# OSO-SAFE-B1-03.net
KiCad netlist of a schematic drawn in EAGLE
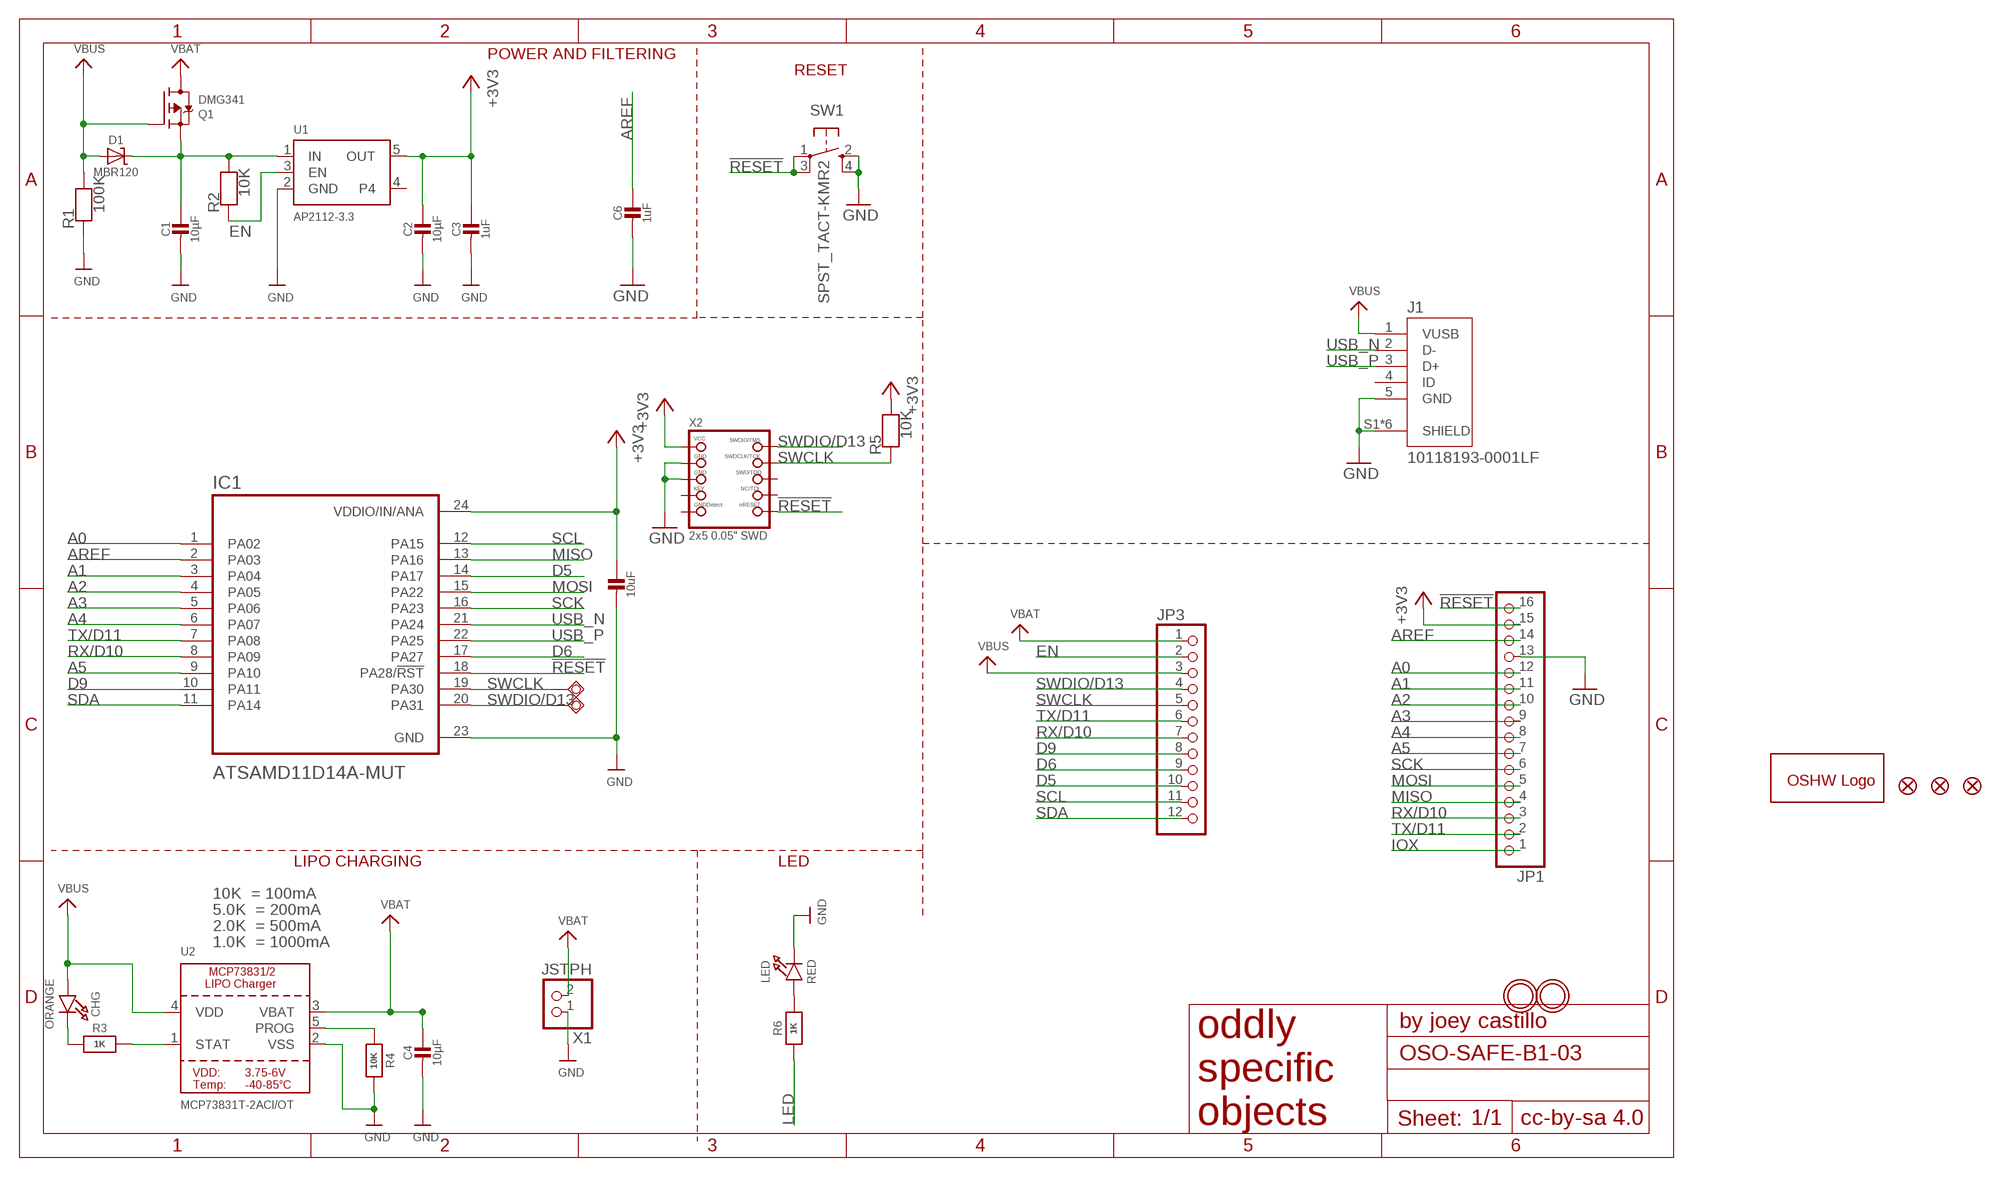
[diagram p0: schematic, sheet 1]

(export (version "E")
  (design (tool "Eeschema 10.0.6"))
  (components
    (comp (ref "C1")
      (value "10µF")
      (footprint "eagle-import:0805-NO")
      (libsource (lib "eagle-import") (part "CAP_CERAMIC0805-NOOUTLINE"))
    )
    (comp (ref "C2")
      (value "10µF")
      (footprint "eagle-import:0805-NO")
      (libsource (lib "eagle-import") (part "CAP_CERAMIC0805-NOOUTLINE"))
    )
    (comp (ref "C3")
      (value "1uF")
      (footprint "eagle-import:0805-NO")
      (libsource (lib "eagle-import") (part "CAP_CERAMIC0805-NOOUTLINE"))
    )
    (comp (ref "C4")
      (value "10µF")
      (footprint "eagle-import:0805-NO")
      (libsource (lib "eagle-import") (part "CAP_CERAMIC0805-NOOUTLINE"))
    )
    (comp (ref "C5")
      (value "10uF")
      (footprint "eagle-import:0805-NO")
      (libsource (lib "eagle-import") (part "CAP_CERAMIC0805-NOOUTLINE"))
    )
    (comp (ref "C6")
      (value "1uF")
      (footprint "eagle-import:0805-NO")
      (libsource (lib "eagle-import") (part "CAP_CERAMIC0805-NOOUTLINE"))
    )
    (comp (ref "CHG")
      (value "ORANGE")
      (footprint "eagle-import:CHIPLED_0805_NOOUTLINE")
      (libsource (lib "eagle-import") (part "LED0805_NOOUTLINE"))
    )
    (comp (ref "D1")
      (value "MBR120")
      (footprint "eagle-import:SOD-123")
      (libsource (lib "eagle-import") (part "DIODE-SCHOTTKYSOD-123"))
    )
    (comp (ref "FID1")
      (value "FIDUCIAL_1MM")
      (footprint "eagle-import:FIDUCIAL_1MM")
      (libsource (lib "eagle-import") (part "FIDUCIAL_1MM"))
    )
    (comp (ref "FID3")
      (value "FIDUCIAL_1MM")
      (footprint "eagle-import:FIDUCIAL_1MM")
      (libsource (lib "eagle-import") (part "FIDUCIAL_1MM"))
    )
    (comp (ref "FID4")
      (value "FIDUCIAL_1MM")
      (footprint "eagle-import:FIDUCIAL_1MM")
      (libsource (lib "eagle-import") (part "FIDUCIAL_1MM"))
    )
    (comp (ref "GOLD_ORB_SM1")
      (value "OSHWLOGOLOGO5MM")
      (footprint "eagle-import:OSHW_5MM")
      (libsource (lib "eagle-import") (part "OSHWLOGOLOGO5MM"))
    )
    (comp (ref "IC1")
      (value "ATSAMD11D14A-MUT")
      (footprint "eagle-import:QFN50P400X400X90-25N")
      (fields (field (name "MF") "Microchip"))
      (libsource (lib "eagle-import") (part "ATSAMD11D14A-MUT"))
    )
    (comp (ref "J1")
      (value "10118193-0001LF")
      (footprint "eagle-import:FCI_10118193-0001LF")
      (fields (field (name "DIGI-KEY_PART_NUMBER") "609-4616-1-ND") (field (name "MF") "Amphenol ICC"))
      (libsource (lib "eagle-import") (part "10118193-0001LF"))
    )
    (comp (ref "JP1")
      (value "HEADER-1X16_MIN")
      (footprint "eagle-import:1X16_ROUND_MIN")
      (libsource (lib "eagle-import") (part "HEADER-1X16_MIN"))
    )
    (comp (ref "JP3")
      (value "HEADER-1X12_MIN")
      (footprint "eagle-import:1X12_ROUND_MIN")
      (libsource (lib "eagle-import") (part "HEADER-1X12_MIN"))
    )
    (comp (ref "LED")
      (value "RED")
      (footprint "eagle-import:CHIPLED_0805_NOOUTLINE")
      (libsource (lib "eagle-import") (part "LED0805_NOOUTLINE"))
    )
    (comp (ref "Q1")
      (value "DMG341")
      (footprint "eagle-import:SOT23-R")
      (libsource (lib "eagle-import") (part "MOSFET-P"))
    )
    (comp (ref "R1")
      (value "100K")
      (footprint "eagle-import:0805-NO")
      (libsource (lib "eagle-import") (part "RESISTOR0805_NOOUTLINE"))
    )
    (comp (ref "R2")
      (value "10K")
      (footprint "eagle-import:0805-NO")
      (libsource (lib "eagle-import") (part "RESISTOR0805_NOOUTLINE"))
    )
    (comp (ref "R3")
      (value "1K")
      (footprint "eagle-import:0805-NO")
      (libsource (lib "eagle-import") (part "RESISTOR0805_NOOUTLINE"))
    )
    (comp (ref "R4")
      (value "10K")
      (footprint "eagle-import:0805-NO")
      (libsource (lib "eagle-import") (part "RESISTOR0805_NOOUTLINE"))
    )
    (comp (ref "R5")
      (value "10K")
      (footprint "eagle-import:0805-NO")
      (libsource (lib "eagle-import") (part "RESISTOR0805_NOOUTLINE"))
    )
    (comp (ref "R6")
      (value "1K")
      (footprint "eagle-import:0805-NO")
      (libsource (lib "eagle-import") (part "RESISTOR0805_NOOUTLINE"))
    )
    (comp (ref "SW1")
      (value "SPST_TACT-KMR2")
      (footprint "eagle-import:KMR2")
      (libsource (lib "eagle-import") (part "SPST_TACT-KMR2"))
    )
    (comp (ref "SWCLK")
      (value "TPSQTP20R")
      (footprint "eagle-import:TP20R")
      (libsource (lib "eagle-import") (part "TPSQTP20R"))
    )
    (comp (ref "SWDIO")
      (value "TPSQTP20R")
      (footprint "eagle-import:TP20R")
      (libsource (lib "eagle-import") (part "TPSQTP20R"))
    )
    (comp (ref "U$31")
      (value "MOUNTINGHOLE2.5")
      (footprint "eagle-import:MOUNTINGHOLE_2.5_PLATED")
      (libsource (lib "eagle-import") (part "MOUNTINGHOLE2.5"))
    )
    (comp (ref "U$32")
      (value "MOUNTINGHOLE2.5")
      (footprint "eagle-import:MOUNTINGHOLE_2.5_PLATED")
      (libsource (lib "eagle-import") (part "MOUNTINGHOLE2.5"))
    )
    (comp (ref "U1")
      (value "AP2112-3.3")
      (footprint "eagle-import:SOT23-5")
      (libsource (lib "eagle-import") (part "VREG_SOT23-5"))
    )
    (comp (ref "U2")
      (value "MCP73831T-2ACI/OT")
      (footprint "eagle-import:SOT23-5")
      (libsource (lib "eagle-import") (part "MCP73831/2"))
    )
    (comp (ref "X1")
      (value "JSTPH")
      (footprint "eagle-import:JSTPH2")
      (libsource (lib "eagle-import") (part "CON_JST_PH_2PIN"))
    )
    (comp (ref "X2")
      (value "2x5 0.05\" SWD")
      (footprint "eagle-import:2X05_1.27MM_BOX_POSTS")
      (libsource (lib "eagle-import") (part "JTAG-CORTEXBOXPOSTS"))
    )
  )
  (nets
    (net (code "1") (name "+3V3") (class "Default")
      (node (ref "C2") (pin "1") (pinfunction "1_1") (pintype "passive"))
      (node (ref "C3") (pin "1") (pinfunction "1_1") (pintype "passive"))
      (node (ref "C5") (pin "1") (pinfunction "1_1") (pintype "passive"))
      (node (ref "IC1") (pin "24") (pinfunction "VDDIO/IN/ANA_24") (pintype "power_in"))
      (node (ref "JP1") (pin "15") (pinfunction "15_15") (pintype "passive"))
      (node (ref "R5") (pin "2") (pinfunction "2_2") (pintype "passive"))
      (node (ref "U1") (pin "5") (pinfunction "OUT_5") (pintype "power_in"))
      (node (ref "X2") (pin "1") (pinfunction "VCC_1") (pintype "power_in"))
    )
    (net (code "2") (name "/A0") (class "Default")
      (node (ref "IC1") (pin "1") (pinfunction "PA02_1") (pintype "bidirectional"))
      (node (ref "JP1") (pin "12") (pinfunction "12_12") (pintype "passive"))
    )
    (net (code "3") (name "/A1") (class "Default")
      (node (ref "IC1") (pin "3") (pinfunction "PA04_3") (pintype "bidirectional"))
      (node (ref "JP1") (pin "11") (pinfunction "11_11") (pintype "passive"))
    )
    (net (code "4") (name "/A2") (class "Default")
      (node (ref "IC1") (pin "4") (pinfunction "PA05_4") (pintype "bidirectional"))
      (node (ref "JP1") (pin "10") (pinfunction "10_10") (pintype "passive"))
    )
    (net (code "5") (name "/A3") (class "Default")
      (node (ref "IC1") (pin "5") (pinfunction "PA06_5") (pintype "bidirectional"))
      (node (ref "JP1") (pin "9") (pinfunction "9_9") (pintype "passive"))
    )
    (net (code "6") (name "/A4") (class "Default")
      (node (ref "IC1") (pin "6") (pinfunction "PA07_6") (pintype "bidirectional"))
      (node (ref "JP1") (pin "8") (pinfunction "8_8") (pintype "passive"))
    )
    (net (code "7") (name "/A5") (class "Default")
      (node (ref "IC1") (pin "9") (pinfunction "PA10_9") (pintype "bidirectional"))
      (node (ref "JP1") (pin "7") (pinfunction "7_7") (pintype "passive"))
    )
    (net (code "8") (name "/AREF") (class "Default")
      (node (ref "C6") (pin "1") (pinfunction "1_1") (pintype "passive"))
      (node (ref "IC1") (pin "2") (pinfunction "PA03_2") (pintype "bidirectional"))
      (node (ref "JP1") (pin "14") (pinfunction "14_14") (pintype "passive"))
    )
    (net (code "9") (name "/D5") (class "Default")
      (node (ref "IC1") (pin "14") (pinfunction "PA17_14") (pintype "bidirectional"))
      (node (ref "JP3") (pin "10") (pinfunction "10_10") (pintype "passive"))
    )
    (net (code "10") (name "/D6") (class "Default")
      (node (ref "IC1") (pin "17") (pinfunction "PA27_17") (pintype "bidirectional"))
      (node (ref "JP3") (pin "9") (pinfunction "9_9") (pintype "passive"))
    )
    (net (code "11") (name "/D9") (class "Default")
      (node (ref "IC1") (pin "10") (pinfunction "PA11_10") (pintype "bidirectional"))
      (node (ref "JP3") (pin "8") (pinfunction "8_8") (pintype "passive"))
    )
    (net (code "12") (name "/EN") (class "Default")
      (node (ref "JP3") (pin "2") (pinfunction "2_2") (pintype "passive"))
      (node (ref "R2") (pin "1") (pinfunction "1_1") (pintype "passive"))
      (node (ref "U1") (pin "3") (pinfunction "EN_3") (pintype "input"))
    )
    (net (code "13") (name "/IOX") (class "Default")
      (node (ref "JP1") (pin "1") (pinfunction "1_1") (pintype "passive"))
    )
    (net (code "14") (name "/LED") (class "Default")
      (node (ref "R6") (pin "1") (pinfunction "1_1") (pintype "passive"))
    )
    (net (code "15") (name "/MISO") (class "Default")
      (node (ref "IC1") (pin "13") (pinfunction "PA16_13") (pintype "bidirectional"))
      (node (ref "JP1") (pin "4") (pinfunction "4_4") (pintype "passive"))
    )
    (net (code "16") (name "/MOSI") (class "Default")
      (node (ref "IC1") (pin "15") (pinfunction "PA22_15") (pintype "bidirectional"))
      (node (ref "JP1") (pin "5") (pinfunction "5_5") (pintype "passive"))
    )
    (net (code "17") (name "/RX{slash}D10") (class "Default")
      (node (ref "IC1") (pin "8") (pinfunction "PA09_8") (pintype "bidirectional"))
      (node (ref "JP1") (pin "3") (pinfunction "3_3") (pintype "passive"))
      (node (ref "JP3") (pin "7") (pinfunction "7_7") (pintype "passive"))
    )
    (net (code "18") (name "/SCK") (class "Default")
      (node (ref "IC1") (pin "16") (pinfunction "PA23_16") (pintype "bidirectional"))
      (node (ref "JP1") (pin "6") (pinfunction "6_6") (pintype "passive"))
    )
    (net (code "19") (name "/SCL") (class "Default")
      (node (ref "IC1") (pin "12") (pinfunction "PA15_12") (pintype "bidirectional"))
      (node (ref "JP3") (pin "11") (pinfunction "11_11") (pintype "passive"))
    )
    (net (code "20") (name "/SDA") (class "Default")
      (node (ref "IC1") (pin "11") (pinfunction "PA14_11") (pintype "bidirectional"))
      (node (ref "JP3") (pin "12") (pinfunction "12_12") (pintype "passive"))
    )
    (net (code "21") (name "/SWCLK") (class "Default")
      (node (ref "IC1") (pin "19") (pinfunction "PA30_19") (pintype "bidirectional"))
      (node (ref "JP3") (pin "5") (pinfunction "5_5") (pintype "passive"))
      (node (ref "R5") (pin "1") (pinfunction "1_1") (pintype "passive"))
      (node (ref "SWCLK") (pin "TP") (pinfunction "TP_TP") (pintype "input"))
      (node (ref "X2") (pin "4") (pinfunction "SWDCLK_4") (pintype "bidirectional"))
    )
    (net (code "22") (name "/SWDIO{slash}D13") (class "Default")
      (node (ref "IC1") (pin "20") (pinfunction "PA31_20") (pintype "bidirectional"))
      (node (ref "JP3") (pin "4") (pinfunction "4_4") (pintype "passive"))
      (node (ref "SWDIO") (pin "TP") (pinfunction "TP_TP") (pintype "input"))
      (node (ref "X2") (pin "2") (pinfunction "SWDIO_2") (pintype "bidirectional"))
    )
    (net (code "23") (name "/TX{slash}D11") (class "Default")
      (node (ref "IC1") (pin "7") (pinfunction "PA08_7") (pintype "bidirectional"))
      (node (ref "JP1") (pin "2") (pinfunction "2_2") (pintype "passive"))
      (node (ref "JP3") (pin "6") (pinfunction "6_6") (pintype "passive"))
    )
    (net (code "24") (name "/USB_N") (class "Default")
      (node (ref "IC1") (pin "21") (pinfunction "PA24_21") (pintype "bidirectional"))
      (node (ref "J1") (pin "2") (pinfunction "D-_2") (pintype "passive"))
    )
    (net (code "25") (name "/USB_P") (class "Default")
      (node (ref "IC1") (pin "22") (pinfunction "PA25_22") (pintype "bidirectional"))
      (node (ref "J1") (pin "3") (pinfunction "D+_3") (pintype "passive"))
    )
    (net (code "26") (name "/~{RESET}") (class "Default")
      (node (ref "IC1") (pin "18") (pinfunction "PA28/~{RST}_18") (pintype "bidirectional"))
      (node (ref "JP1") (pin "16") (pinfunction "16_16") (pintype "passive"))
      (node (ref "SW1") (pin "1") (pinfunction "P_1") (pintype "passive"))
      (node (ref "SW1") (pin "3") (pinfunction "P1_3") (pintype "passive"))
      (node (ref "X2") (pin "10") (pinfunction "NRESET_10") (pintype "bidirectional"))
    )
    (net (code "27") (name "GND") (class "Default")
      (node (ref "C1") (pin "2") (pinfunction "2_2") (pintype "passive"))
      (node (ref "C2") (pin "2") (pinfunction "2_2") (pintype "passive"))
      (node (ref "C3") (pin "2") (pinfunction "2_2") (pintype "passive"))
      (node (ref "C4") (pin "2") (pinfunction "2_2") (pintype "passive"))
      (node (ref "C5") (pin "2") (pinfunction "2_2") (pintype "passive"))
      (node (ref "C6") (pin "2") (pinfunction "2_2") (pintype "passive"))
      (node (ref "IC1") (pin "23") (pinfunction "GND_23") (pintype "power_in"))
      (node (ref "J1") (pin "5") (pinfunction "GND_5") (pintype "passive"))
      (node (ref "J1") (pin "S1") (pinfunction "SHIELD_S1") (pintype "passive"))
      (node (ref "J1") (pin "S2") (pinfunction "SHIELD_S2") (pintype "passive"))
      (node (ref "J1") (pin "S3") (pinfunction "SHIELD_S3") (pintype "passive"))
      (node (ref "J1") (pin "S4") (pinfunction "SHIELD_S4") (pintype "passive"))
      (node (ref "J1") (pin "S5") (pinfunction "SHIELD_S5") (pintype "passive"))
      (node (ref "J1") (pin "S6") (pinfunction "SHIELD_S6") (pintype "passive"))
      (node (ref "JP1") (pin "13") (pinfunction "13_13") (pintype "passive"))
      (node (ref "LED") (pin "C") (pinfunction "C_C") (pintype "passive"))
      (node (ref "R1") (pin "1") (pinfunction "1_1") (pintype "passive"))
      (node (ref "R4") (pin "2") (pinfunction "2_2") (pintype "passive"))
      (node (ref "SW1") (pin "2") (pinfunction "S_2") (pintype "passive"))
      (node (ref "SW1") (pin "4") (pinfunction "S1_4") (pintype "passive"))
      (node (ref "U1") (pin "2") (pinfunction "GND_2") (pintype "power_in"))
      (node (ref "U2") (pin "2") (pinfunction "VSS_2") (pintype "power_in"))
      (node (ref "X1") (pin "1") (pinfunction "1_1") (pintype "passive"))
      (node (ref "X2") (pin "3") (pinfunction "GND_3") (pintype "power_in"))
      (node (ref "X2") (pin "5") (pinfunction "GND_5") (pintype "power_in"))
    )
    (net (code "28") (name "Net-(CHG-PadC)") (class "Default")
      (node (ref "CHG") (pin "C") (pinfunction "C_C") (pintype "passive"))
      (node (ref "R3") (pin "1") (pinfunction "1_1") (pintype "passive"))
    )
    (net (code "29") (name "Net-(LED-PadA)") (class "Default")
      (node (ref "LED") (pin "A") (pinfunction "A_A") (pintype "passive"))
      (node (ref "R6") (pin "2") (pinfunction "2_2") (pintype "passive"))
    )
    (net (code "30") (name "Net-(Q1-S)") (class "Default")
      (node (ref "C1") (pin "1") (pinfunction "1_1") (pintype "passive"))
      (node (ref "D1") (pin "C") (pinfunction "C_C") (pintype "passive"))
      (node (ref "Q1") (pin "2") (pinfunction "S_2") (pintype "passive"))
      (node (ref "R2") (pin "2") (pinfunction "2_2") (pintype "passive"))
      (node (ref "U1") (pin "1") (pinfunction "IN_1") (pintype "power_in"))
    )
    (net (code "31") (name "Net-(U2-PROG)") (class "Default")
      (node (ref "R4") (pin "1") (pinfunction "1_1") (pintype "passive"))
      (node (ref "U2") (pin "5") (pinfunction "PROG_5") (pintype "input"))
    )
    (net (code "32") (name "Net-(U2-STAT)") (class "Default")
      (node (ref "R3") (pin "2") (pinfunction "2_2") (pintype "passive"))
      (node (ref "U2") (pin "1") (pinfunction "STAT_1") (pintype "output"))
    )
    (net (code "33") (name "VBAT") (class "Default")
      (node (ref "C4") (pin "1") (pinfunction "1_1") (pintype "passive"))
      (node (ref "JP3") (pin "1") (pinfunction "1_1") (pintype "passive"))
      (node (ref "Q1") (pin "3") (pinfunction "D_3") (pintype "passive"))
      (node (ref "U2") (pin "3") (pinfunction "VBAT_3") (pintype "power_in"))
      (node (ref "X1") (pin "2") (pinfunction "2_2") (pintype "passive"))
    )
    (net (code "34") (name "VBUS") (class "Default")
      (node (ref "CHG") (pin "A") (pinfunction "A_A") (pintype "passive"))
      (node (ref "D1") (pin "A") (pinfunction "A_A") (pintype "passive"))
      (node (ref "J1") (pin "1") (pinfunction "VUSB_1") (pintype "passive"))
      (node (ref "JP3") (pin "3") (pinfunction "3_3") (pintype "passive"))
      (node (ref "Q1") (pin "1") (pinfunction "G_1") (pintype "passive"))
      (node (ref "R1") (pin "2") (pinfunction "2_2") (pintype "passive"))
      (node (ref "U2") (pin "4") (pinfunction "VDD_4") (pintype "power_in"))
    )
    (net (code "35") (name "unconnected-(J1-ID-Pad4)") (class "Default")
      (node (ref "J1") (pin "4") (pinfunction "ID_4") (pintype "passive"))
    )
    (net (code "36") (name "unconnected-(U1-P4-Pad4)") (class "Default")
      (node (ref "U1") (pin "4") (pinfunction "P4_4") (pintype "bidirectional"))
    )
    (net (code "37") (name "unconnected-(X2-GNDDETECT-Pad9)") (class "Default")
      (node (ref "X2") (pin "9") (pinfunction "GNDDETECT_9") (pintype "bidirectional"))
    )
    (net (code "38") (name "unconnected-(X2-KEY-Pad7)") (class "Default")
      (node (ref "X2") (pin "7") (pinfunction "KEY_7") (pintype "bidirectional"))
    )
    (net (code "39") (name "unconnected-(X2-SWO-Pad6)") (class "Default")
      (node (ref "X2") (pin "6") (pinfunction "SWO_6") (pintype "bidirectional"))
    )
    (net (code "40") (name "unconnected-(X2-TDI-Pad8)") (class "Default")
      (node (ref "X2") (pin "8") (pinfunction "TDI_8") (pintype "bidirectional"))
    )
  )
)
